# fibonacci.net
KiCad netlist of a schematic drawn in EAGLE
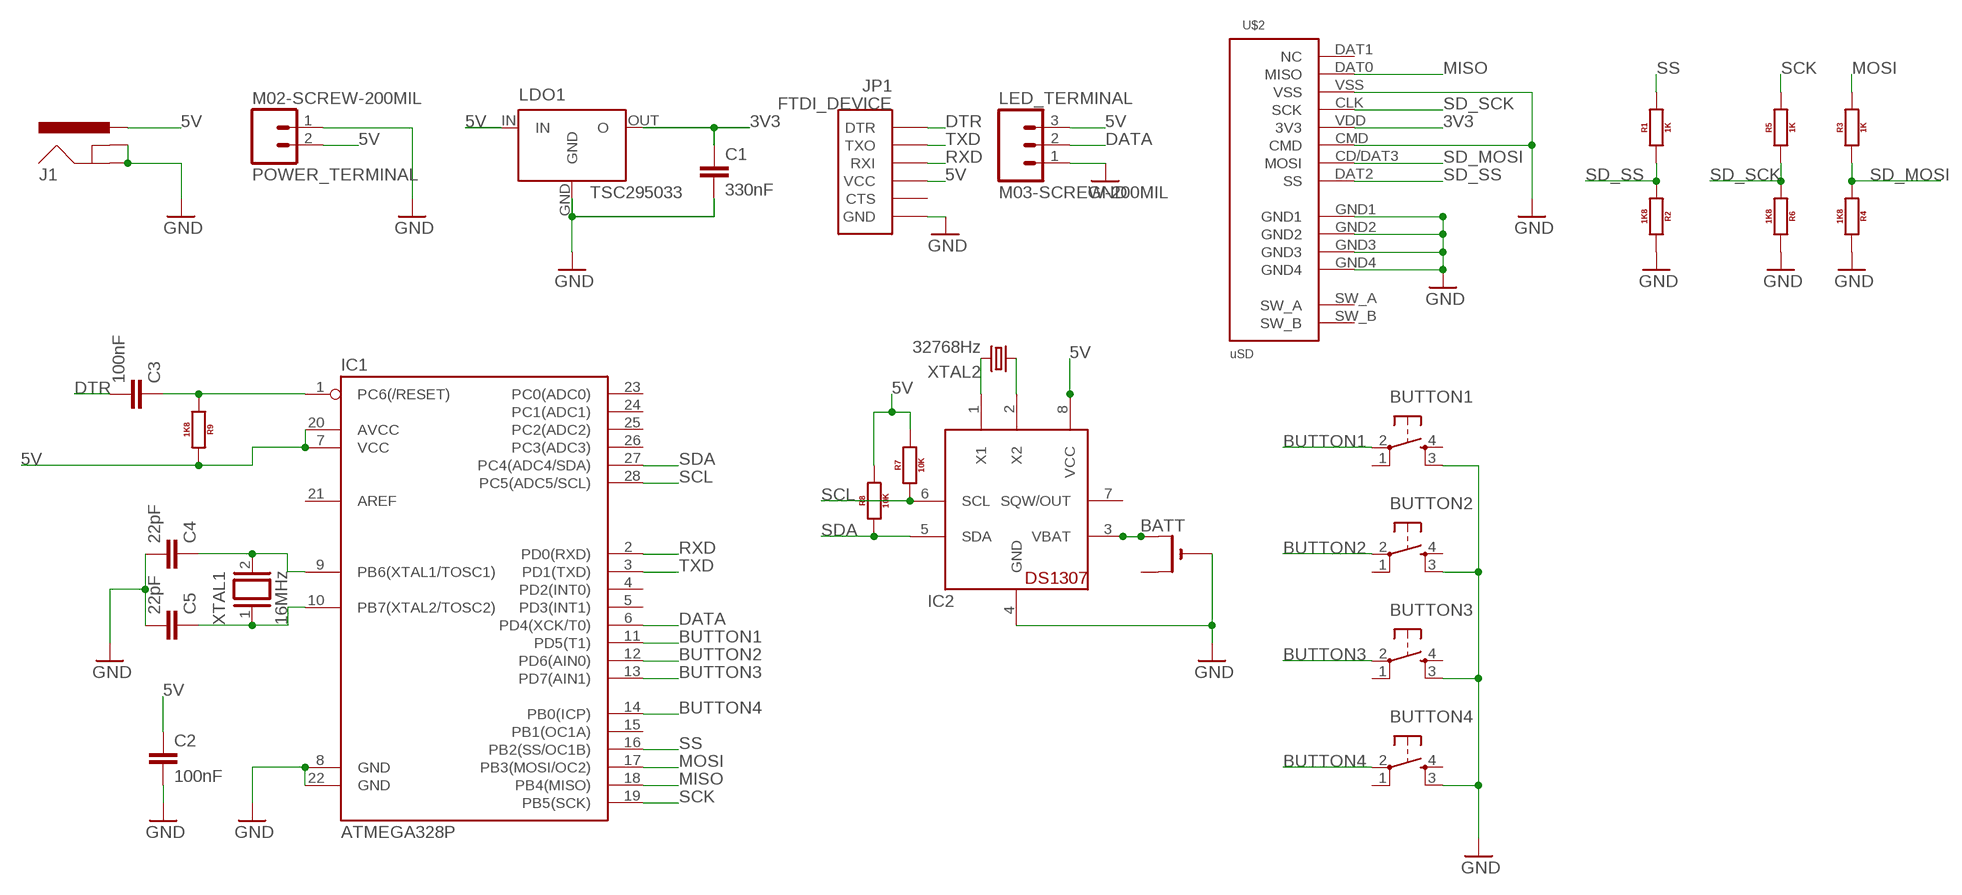
[diagram p0: schematic, sheet 1]

(export (version "E")
  (design (tool "Eeschema 10.0.6"))
  (components
    (comp (ref "BATT")
      (value "CR2032SMT")
      (footprint "eagle-import:CR2032-SMD")
      (libsource (lib "eagle-import") (part "CR2032SMT"))
    )
    (comp (ref "BUTTON1")
      (value "B1")
      (footprint "eagle-import:TACTILE_BUTTON")
      (libsource (lib "eagle-import") (part "TACTILE_BUTTON"))
    )
    (comp (ref "BUTTON2")
      (value "B2")
      (footprint "eagle-import:TACTILE_BUTTON")
      (libsource (lib "eagle-import") (part "TACTILE_BUTTON"))
    )
    (comp (ref "BUTTON3")
      (value "B3")
      (footprint "eagle-import:TACTILE_BUTTON")
      (libsource (lib "eagle-import") (part "TACTILE_BUTTON"))
    )
    (comp (ref "BUTTON4")
      (value "B4")
      (footprint "eagle-import:TACTILE_BUTTON")
      (libsource (lib "eagle-import") (part "TACTILE_BUTTON"))
    )
    (comp (ref "C1")
      (value "330nF")
      (footprint "eagle-import:C050-025X075")
      (libsource (lib "eagle-import") (part "C-EU050-025X075"))
    )
    (comp (ref "C2")
      (value "100nF")
      (footprint "eagle-import:C050-025X075")
      (libsource (lib "eagle-import") (part "C-EU050-025X075"))
    )
    (comp (ref "C3")
      (value "100nF")
      (footprint "eagle-import:C050-025X075")
      (libsource (lib "eagle-import") (part "C-EU050-025X075"))
    )
    (comp (ref "C4")
      (value "22pF")
      (footprint "eagle-import:C050-025X075")
      (libsource (lib "eagle-import") (part "C-EU050-025X075"))
    )
    (comp (ref "C5")
      (value "22pF")
      (footprint "eagle-import:C050-025X075")
      (libsource (lib "eagle-import") (part "C-EU050-025X075"))
    )
    (comp (ref "IC1")
      (value "ATMEGA328P")
      (footprint "eagle-import:DIL28-3")
      (libsource (lib "eagle-import") (part "ATMEGA328P_PDIP"))
    )
    (comp (ref "IC2")
      (value "DS1307")
      (footprint "eagle-import:DIL08")
      (libsource (lib "eagle-import") (part "DS1307"))
    )
    (comp (ref "J1")
      (value "POWER_JACKPTH")
      (footprint "eagle-import:POWER_JACK_PTH")
      (libsource (lib "eagle-import") (part "POWER_JACKPTH"))
    )
    (comp (ref "JP1")
      (value "FTDI_DEVICE")
      (footprint "eagle-import:FTDI_DEVICE_SIDE")
      (libsource (lib "eagle-import") (part "FTDI_DEVICE"))
    )
    (comp (ref "LDO1")
      (value "TSC295033")
      (footprint "eagle-import:TO92")
      (fields (field (name "MF") "NATIONAL SEMICONDUCTOR") (field (name "MPN") "LP2950CZ-5.0/NOPB"))
      (libsource (lib "eagle-import") (part "LP2950Z"))
    )
    (comp (ref "LED_TERMINAL")
      (value "M03-SCREW-200MIL")
      (footprint "eagle-import:SCREWTERMINAL-200MIL-3")
      (libsource (lib "eagle-import") (part "M03-SCREW-200MIL"))
    )
    (comp (ref "POWER_TERMINAL")
      (value "M02-SCREW-200MIL")
      (footprint "eagle-import:SCREWTERMINAL-200MIL-2")
      (libsource (lib "eagle-import") (part "M02-SCREW-200MIL"))
    )
    (comp (ref "R1")
      (value "1K")
      (footprint "eagle-import:AXIAL-0.4")
      (libsource (lib "eagle-import") (part "RESISTOR"))
    )
    (comp (ref "R2")
      (value "1K8")
      (footprint "eagle-import:AXIAL-0.4")
      (libsource (lib "eagle-import") (part "RESISTOR"))
    )
    (comp (ref "R3")
      (value "1K")
      (footprint "eagle-import:AXIAL-0.4")
      (libsource (lib "eagle-import") (part "RESISTOR"))
    )
    (comp (ref "R4")
      (value "1K8")
      (footprint "eagle-import:AXIAL-0.4")
      (libsource (lib "eagle-import") (part "RESISTOR"))
    )
    (comp (ref "R5")
      (value "1K")
      (footprint "eagle-import:AXIAL-0.4")
      (libsource (lib "eagle-import") (part "RESISTOR"))
    )
    (comp (ref "R6")
      (value "1K8")
      (footprint "eagle-import:AXIAL-0.4")
      (libsource (lib "eagle-import") (part "RESISTOR"))
    )
    (comp (ref "R7")
      (value "10K")
      (footprint "eagle-import:AXIAL-0.4")
      (libsource (lib "eagle-import") (part "RESISTOR"))
    )
    (comp (ref "R8")
      (value "10K")
      (footprint "eagle-import:AXIAL-0.4")
      (libsource (lib "eagle-import") (part "RESISTOR"))
    )
    (comp (ref "R9")
      (value "1K8")
      (footprint "eagle-import:AXIAL-0.4")
      (libsource (lib "eagle-import") (part "RESISTOR"))
    )
    (comp (ref "U$2")
      (value "uSD")
      (footprint "eagle-import:DM3D")
      (libsource (lib "eagle-import") (part "MICROSD-HRS_DM3D"))
    )
    (comp (ref "XTAL1")
      (value "16MHz")
      (footprint "eagle-import:QS")
      (libsource (lib "eagle-import") (part "XTAL/S"))
    )
    (comp (ref "XTAL2")
      (value "32768Hz")
      (footprint "eagle-import:TC38H")
      (libsource (lib "eagle-import") (part "CRYSTAL_TC38H"))
    )
  )
  (nets
    (net (code "1") (name "/3V3") (class "Default")
      (node (ref "C1") (pin "1") (pinfunction "1_1") (pintype "passive"))
      (node (ref "LDO1") (pin "OUT") (pinfunction "O_OUT") (pintype "output"))
      (node (ref "U$2") (pin "VDD") (pinfunction "3V3_VDD") (pintype "bidirectional"))
    )
    (net (code "2") (name "/5V") (class "Default")
      (node (ref "C2") (pin "1") (pinfunction "1_1") (pintype "passive"))
      (node (ref "IC1") (pin "20") (pinfunction "AVCC_20") (pintype "bidirectional"))
      (node (ref "IC1") (pin "7") (pinfunction "VCC_7") (pintype "bidirectional"))
      (node (ref "IC2") (pin "8") (pinfunction "VCC_8") (pintype "power_in"))
      (node (ref "J1") (pin "PWR") (pinfunction "PWR_PWR") (pintype "bidirectional"))
      (node (ref "JP1") (pin "P$4") (pinfunction "VCC_P$4") (pintype "bidirectional"))
      (node (ref "LDO1") (pin "IN") (pinfunction "IN_IN") (pintype "input"))
      (node (ref "LED_TERMINAL") (pin "3") (pinfunction "3_3") (pintype "passive"))
      (node (ref "POWER_TERMINAL") (pin "2") (pinfunction "2_2") (pintype "passive"))
      (node (ref "R7") (pin "P$2") (pinfunction "2_P$2") (pintype "passive"))
      (node (ref "R8") (pin "P$2") (pinfunction "2_P$2") (pintype "passive"))
      (node (ref "R9") (pin "P$2") (pinfunction "2_P$2") (pintype "passive"))
    )
    (net (code "3") (name "/BUTTON1") (class "Default")
      (node (ref "BUTTON1") (pin "2") (pinfunction "SWA1_2") (pintype "passive"))
      (node (ref "IC1") (pin "11") (pinfunction "PD5(T1)_11") (pintype "bidirectional"))
    )
    (net (code "4") (name "/BUTTON2") (class "Default")
      (node (ref "BUTTON2") (pin "2") (pinfunction "SWA1_2") (pintype "passive"))
      (node (ref "IC1") (pin "12") (pinfunction "PD6(AIN0)_12") (pintype "bidirectional"))
    )
    (net (code "5") (name "/BUTTON3") (class "Default")
      (node (ref "BUTTON3") (pin "2") (pinfunction "SWA1_2") (pintype "passive"))
      (node (ref "IC1") (pin "13") (pinfunction "PD7(AIN1)_13") (pintype "bidirectional"))
    )
    (net (code "6") (name "/BUTTON4") (class "Default")
      (node (ref "BUTTON4") (pin "2") (pinfunction "SWA1_2") (pintype "passive"))
      (node (ref "IC1") (pin "14") (pinfunction "PB0(ICP)_14") (pintype "bidirectional"))
    )
    (net (code "7") (name "/DATA") (class "Default")
      (node (ref "IC1") (pin "6") (pinfunction "PD4(XCK/T0)_6") (pintype "bidirectional"))
      (node (ref "LED_TERMINAL") (pin "2") (pinfunction "2_2") (pintype "passive"))
    )
    (net (code "8") (name "/DTR") (class "Default")
      (node (ref "C3") (pin "2") (pinfunction "2_2") (pintype "passive"))
      (node (ref "JP1") (pin "P$1") (pinfunction "DTR_P$1") (pintype "bidirectional"))
    )
    (net (code "9") (name "/MISO") (class "Default")
      (node (ref "IC1") (pin "18") (pinfunction "PB4(MISO)_18") (pintype "bidirectional"))
      (node (ref "U$2") (pin "DAT0") (pinfunction "MISO_DAT0") (pintype "bidirectional"))
    )
    (net (code "10") (name "/MOSI") (class "Default")
      (node (ref "IC1") (pin "17") (pinfunction "PB3(MOSI/OC2)_17") (pintype "bidirectional"))
      (node (ref "R3") (pin "P$2") (pinfunction "2_P$2") (pintype "passive"))
    )
    (net (code "11") (name "/RXD") (class "Default")
      (node (ref "IC1") (pin "2") (pinfunction "PD0(RXD)_2") (pintype "bidirectional"))
      (node (ref "JP1") (pin "P$3") (pinfunction "RXI_P$3") (pintype "bidirectional"))
    )
    (net (code "12") (name "/SCK") (class "Default")
      (node (ref "IC1") (pin "19") (pinfunction "PB5(SCK)_19") (pintype "bidirectional"))
      (node (ref "R5") (pin "P$2") (pinfunction "2_P$2") (pintype "passive"))
    )
    (net (code "13") (name "/SCL") (class "Default")
      (node (ref "IC1") (pin "28") (pinfunction "PC5(ADC5/SCL)_28") (pintype "bidirectional"))
      (node (ref "IC2") (pin "6") (pinfunction "SCL_6") (pintype "bidirectional"))
      (node (ref "R7") (pin "P$1") (pinfunction "1_P$1") (pintype "passive"))
    )
    (net (code "14") (name "/SDA") (class "Default")
      (node (ref "IC1") (pin "27") (pinfunction "PC4(ADC4/SDA)_27") (pintype "bidirectional"))
      (node (ref "IC2") (pin "5") (pinfunction "SDA_5") (pintype "bidirectional"))
      (node (ref "R8") (pin "P$1") (pinfunction "1_P$1") (pintype "passive"))
    )
    (net (code "15") (name "/SD_MOSI") (class "Default")
      (node (ref "R3") (pin "P$1") (pinfunction "1_P$1") (pintype "passive"))
      (node (ref "R4") (pin "P$1") (pinfunction "1_P$1") (pintype "passive"))
      (node (ref "U$2") (pin "CD/DAT3") (pinfunction "MOSI_CD/DAT3") (pintype "bidirectional"))
    )
    (net (code "16") (name "/SD_SCK") (class "Default")
      (node (ref "R5") (pin "P$1") (pinfunction "1_P$1") (pintype "passive"))
      (node (ref "R6") (pin "P$1") (pinfunction "1_P$1") (pintype "passive"))
      (node (ref "U$2") (pin "CLK") (pinfunction "SCK_CLK") (pintype "bidirectional"))
    )
    (net (code "17") (name "/SD_SS") (class "Default")
      (node (ref "R1") (pin "P$1") (pinfunction "1_P$1") (pintype "passive"))
      (node (ref "R2") (pin "P$1") (pinfunction "1_P$1") (pintype "passive"))
      (node (ref "U$2") (pin "DAT2") (pinfunction "SS_DAT2") (pintype "bidirectional"))
    )
    (net (code "18") (name "/SS") (class "Default")
      (node (ref "IC1") (pin "16") (pinfunction "PB2(SS/OC1B)_16") (pintype "bidirectional"))
      (node (ref "R1") (pin "P$2") (pinfunction "2_P$2") (pintype "passive"))
    )
    (net (code "19") (name "/TXD") (class "Default")
      (node (ref "IC1") (pin "3") (pinfunction "PD1(TXD)_3") (pintype "bidirectional"))
      (node (ref "JP1") (pin "P$2") (pinfunction "TXO_P$2") (pintype "bidirectional"))
    )
    (net (code "20") (name "GND") (class "Default")
      (node (ref "BATT") (pin "-") (pinfunction "-_-") (pintype "passive"))
      (node (ref "BUTTON1") (pin "3") (pinfunction "SWB2_3") (pintype "passive"))
      (node (ref "BUTTON2") (pin "3") (pinfunction "SWB2_3") (pintype "passive"))
      (node (ref "BUTTON3") (pin "3") (pinfunction "SWB2_3") (pintype "passive"))
      (node (ref "BUTTON4") (pin "3") (pinfunction "SWB2_3") (pintype "passive"))
      (node (ref "C1") (pin "2") (pinfunction "2_2") (pintype "passive"))
      (node (ref "C2") (pin "2") (pinfunction "2_2") (pintype "passive"))
      (node (ref "C4") (pin "2") (pinfunction "2_2") (pintype "passive"))
      (node (ref "C5") (pin "2") (pinfunction "2_2") (pintype "passive"))
      (node (ref "IC1") (pin "22") (pinfunction "GND_22") (pintype "bidirectional"))
      (node (ref "IC1") (pin "8") (pinfunction "GND_8") (pintype "bidirectional"))
      (node (ref "IC2") (pin "4") (pinfunction "GND_4") (pintype "power_in"))
      (node (ref "J1") (pin "GND") (pinfunction "GND_GND") (pintype "bidirectional"))
      (node (ref "J1") (pin "GNDBREAK") (pinfunction "GNDBREAK_GNDBREAK") (pintype "bidirectional"))
      (node (ref "JP1") (pin "P$6") (pinfunction "GND_P$6") (pintype "bidirectional"))
      (node (ref "LDO1") (pin "GND") (pinfunction "GND_GND") (pintype "power_in"))
      (node (ref "LED_TERMINAL") (pin "1") (pinfunction "1_1") (pintype "passive"))
      (node (ref "POWER_TERMINAL") (pin "1") (pinfunction "1_1") (pintype "passive"))
      (node (ref "R2") (pin "P$2") (pinfunction "2_P$2") (pintype "passive"))
      (node (ref "R4") (pin "P$2") (pinfunction "2_P$2") (pintype "passive"))
      (node (ref "R6") (pin "P$2") (pinfunction "2_P$2") (pintype "passive"))
      (node (ref "U$2") (pin "CMD") (pinfunction "CMD_CMD") (pintype "bidirectional"))
      (node (ref "U$2") (pin "GND1") (pinfunction "GND1_GND1") (pintype "bidirectional"))
      (node (ref "U$2") (pin "GND2") (pinfunction "GND2_GND2") (pintype "bidirectional"))
      (node (ref "U$2") (pin "GND3") (pinfunction "GND3_GND3") (pintype "bidirectional"))
      (node (ref "U$2") (pin "GND4") (pinfunction "GND4_GND4") (pintype "bidirectional"))
      (node (ref "U$2") (pin "VSS") (pinfunction "VSS_VSS") (pintype "bidirectional"))
    )
    (net (code "21") (name "Net-(BATT-+)") (class "Default")
      (node (ref "BATT") (pin "+$1") (pinfunction "+_+$1") (pintype "passive"))
      (node (ref "IC2") (pin "3") (pinfunction "VBAT_3") (pintype "power_in"))
    )
    (net (code "22") (name "Net-(IC1-PB6(XTAL1{slash}TOSC1))") (class "Default")
      (node (ref "C4") (pin "1") (pinfunction "1_1") (pintype "passive"))
      (node (ref "IC1") (pin "9") (pinfunction "PB6(XTAL1/TOSC1)_9") (pintype "bidirectional"))
      (node (ref "XTAL1") (pin "2") (pinfunction "2_2") (pintype "passive"))
    )
    (net (code "23") (name "Net-(IC1-PB7(XTAL2{slash}TOSC2))") (class "Default")
      (node (ref "C5") (pin "1") (pinfunction "1_1") (pintype "passive"))
      (node (ref "IC1") (pin "10") (pinfunction "PB7(XTAL2/TOSC2)_10") (pintype "bidirectional"))
      (node (ref "XTAL1") (pin "1") (pinfunction "1_1") (pintype "passive"))
    )
    (net (code "24") (name "Net-(IC1-PC6({slash}RESET))") (class "Default")
      (node (ref "C3") (pin "1") (pinfunction "1_1") (pintype "passive"))
      (node (ref "IC1") (pin "1") (pinfunction "PC6(/RESET)_1") (pintype "bidirectional"))
      (node (ref "R9") (pin "P$1") (pinfunction "1_P$1") (pintype "passive"))
    )
    (net (code "25") (name "Net-(IC2-X1)") (class "Default")
      (node (ref "IC2") (pin "1") (pinfunction "X1_1") (pintype "passive"))
      (node (ref "XTAL2") (pin "2") (pinfunction "2_2") (pintype "passive"))
    )
    (net (code "26") (name "Net-(IC2-X2)") (class "Default")
      (node (ref "IC2") (pin "2") (pinfunction "X2_2") (pintype "passive"))
      (node (ref "XTAL2") (pin "1") (pinfunction "1_1") (pintype "passive"))
    )
    (net (code "27") (name "unconnected-(BATT-+1-Pad+$2)") (class "Default")
      (node (ref "BATT") (pin "+$2") (pinfunction "+1_+$2") (pintype "passive"))
    )
    (net (code "28") (name "unconnected-(BUTTON1-SWA2-Pad4)") (class "Default")
      (node (ref "BUTTON1") (pin "4") (pinfunction "SWA2_4") (pintype "passive"))
    )
    (net (code "29") (name "unconnected-(BUTTON1-SWB1-Pad1)") (class "Default")
      (node (ref "BUTTON1") (pin "1") (pinfunction "SWB1_1") (pintype "passive"))
    )
    (net (code "30") (name "unconnected-(BUTTON2-SWA2-Pad4)") (class "Default")
      (node (ref "BUTTON2") (pin "4") (pinfunction "SWA2_4") (pintype "passive"))
    )
    (net (code "31") (name "unconnected-(BUTTON2-SWB1-Pad1)") (class "Default")
      (node (ref "BUTTON2") (pin "1") (pinfunction "SWB1_1") (pintype "passive"))
    )
    (net (code "32") (name "unconnected-(BUTTON3-SWA2-Pad4)") (class "Default")
      (node (ref "BUTTON3") (pin "4") (pinfunction "SWA2_4") (pintype "passive"))
    )
    (net (code "33") (name "unconnected-(BUTTON3-SWB1-Pad1)") (class "Default")
      (node (ref "BUTTON3") (pin "1") (pinfunction "SWB1_1") (pintype "passive"))
    )
    (net (code "34") (name "unconnected-(BUTTON4-SWA2-Pad4)") (class "Default")
      (node (ref "BUTTON4") (pin "4") (pinfunction "SWA2_4") (pintype "passive"))
    )
    (net (code "35") (name "unconnected-(BUTTON4-SWB1-Pad1)") (class "Default")
      (node (ref "BUTTON4") (pin "1") (pinfunction "SWB1_1") (pintype "passive"))
    )
    (net (code "36") (name "unconnected-(IC1-AREF-Pad21)") (class "Default")
      (node (ref "IC1") (pin "21") (pinfunction "AREF_21") (pintype "bidirectional"))
    )
    (net (code "37") (name "unconnected-(IC1-PB1(OC1A)-Pad15)") (class "Default")
      (node (ref "IC1") (pin "15") (pinfunction "PB1(OC1A)_15") (pintype "bidirectional"))
    )
    (net (code "38") (name "unconnected-(IC1-PC0(ADC0)-Pad23)") (class "Default")
      (node (ref "IC1") (pin "23") (pinfunction "PC0(ADC0)_23") (pintype "bidirectional"))
    )
    (net (code "39") (name "unconnected-(IC1-PC1(ADC1)-Pad24)") (class "Default")
      (node (ref "IC1") (pin "24") (pinfunction "PC1(ADC1)_24") (pintype "bidirectional"))
    )
    (net (code "40") (name "unconnected-(IC1-PC2(ADC2)-Pad25)") (class "Default")
      (node (ref "IC1") (pin "25") (pinfunction "PC2(ADC2)_25") (pintype "bidirectional"))
    )
    (net (code "41") (name "unconnected-(IC1-PC3(ADC3)-Pad26)") (class "Default")
      (node (ref "IC1") (pin "26") (pinfunction "PC3(ADC3)_26") (pintype "bidirectional"))
    )
    (net (code "42") (name "unconnected-(IC1-PD2(INT0)-Pad4)") (class "Default")
      (node (ref "IC1") (pin "4") (pinfunction "PD2(INT0)_4") (pintype "bidirectional"))
    )
    (net (code "43") (name "unconnected-(IC1-PD3(INT1)-Pad5)") (class "Default")
      (node (ref "IC1") (pin "5") (pinfunction "PD3(INT1)_5") (pintype "bidirectional"))
    )
    (net (code "44") (name "unconnected-(IC2-SQW{slash}OUT-Pad7)") (class "Default")
      (node (ref "IC2") (pin "7") (pinfunction "SQW/OUT_7") (pintype "bidirectional"))
    )
    (net (code "45") (name "unconnected-(JP1-CTS-PadP$5)") (class "Default")
      (node (ref "JP1") (pin "P$5") (pinfunction "CTS_P$5") (pintype "bidirectional"))
    )
    (net (code "46") (name "unconnected-(U$2-NC-PadDAT1)") (class "Default")
      (node (ref "U$2") (pin "DAT1") (pinfunction "NC_DAT1") (pintype "bidirectional"))
    )
    (net (code "47") (name "unconnected-(U$2-PadSW_A)") (class "Default")
      (node (ref "U$2") (pin "SW_A") (pinfunction "SW_A_SW_A") (pintype "bidirectional"))
    )
    (net (code "48") (name "unconnected-(U$2-PadSW_B)") (class "Default")
      (node (ref "U$2") (pin "SW_B") (pinfunction "SW_B_SW_B") (pintype "bidirectional"))
    )
  )
)
